# XBee.net
KiCad netlist of a schematic drawn in Altium Designer
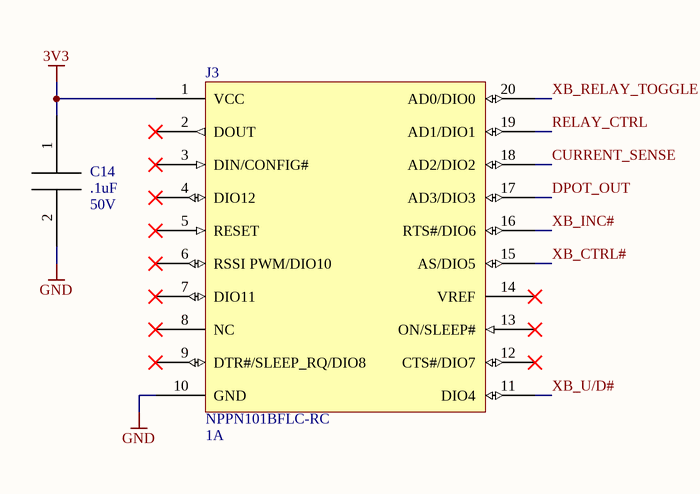
[diagram p0: XBee.SchDoc]

(export (version "E")
  (design (tool "Eeschema 10.0.6"))
  (components
    (comp (ref "C14")
      (value ".1uF")
      (footprint "0603")
      (fields (field (name "RATING") "50V") (field (name "Comment") "C_CAP_0603"))
      (libsource (lib "SeniorProject") (part "C_CAP_0603"))
    )
    (comp (ref "J3")
      (value "J_XBEE_NPPN101BFLC-RC")
      (footprint "NPPN101BFLC-RC")
      (fields
        (field (name "MANUFACTURER") "Sullins Connector Solutions")
        (field (name "PARTNUMBER") "NPPN101BFLC-RC")
        (field (name "RATING") "1A")
      )
      (libsource (lib "SeniorProject") (part "J_XBEE_NPPN101BFLC-RC"))
    )
  )
  (nets
    (net (code "1") (name "/CURRENT_SENSE") (class "Default")
      (node (ref "J3") (pin "18") (pinfunction "AD2/DIO2_18") (pintype "bidirectional"))
    )
    (net (code "2") (name "/DPOT_OUT") (class "Default")
      (node (ref "J3") (pin "17") (pinfunction "AD3/DIO3_17") (pintype "bidirectional"))
    )
    (net (code "3") (name "/RELAY_CTRL") (class "Default")
      (node (ref "J3") (pin "19") (pinfunction "AD1/DIO1_19") (pintype "bidirectional"))
    )
    (net (code "4") (name "/XB_CTRL#") (class "Default")
      (node (ref "J3") (pin "15") (pinfunction "AS/DIO5_15") (pintype "bidirectional"))
    )
    (net (code "5") (name "/XB_INC#") (class "Default")
      (node (ref "J3") (pin "16") (pinfunction "RTS#/DIO6_16") (pintype "bidirectional"))
    )
    (net (code "6") (name "/XB_RELAY_TOGGLE") (class "Default")
      (node (ref "J3") (pin "20") (pinfunction "AD0/DIO0_20") (pintype "bidirectional"))
    )
    (net (code "7") (name "/XB_U{slash}D#") (class "Default")
      (node (ref "J3") (pin "11") (pinfunction "DIO4_11") (pintype "bidirectional"))
    )
    (net (code "8") (name "3V3") (class "Default")
      (node (ref "C14") (pin "1") (pintype "passive"))
      (node (ref "J3") (pin "1") (pinfunction "VCC_1") (pintype "power_in"))
    )
    (net (code "9") (name "GND") (class "Default")
      (node (ref "C14") (pin "2") (pintype "passive"))
      (node (ref "J3") (pin "10") (pinfunction "GND_10") (pintype "power_in"))
    )
    (net (code "10") (name "unconnected-(J3-CTS#{slash}DIO7-Pad12)") (class "Default")
      (node (ref "J3") (pin "12") (pinfunction "CTS#/DIO7_12") (pintype "bidirectional+no_connect"))
    )
    (net (code "11") (name "unconnected-(J3-DIN{slash}CONFIG#-Pad3)") (class "Default")
      (node (ref "J3") (pin "3") (pinfunction "DIN/CONFIG#_3") (pintype "input+no_connect"))
    )
    (net (code "12") (name "unconnected-(J3-DIO11-Pad7)") (class "Default")
      (node (ref "J3") (pin "7") (pinfunction "DIO11_7") (pintype "bidirectional+no_connect"))
    )
    (net (code "13") (name "unconnected-(J3-DIO12-Pad4)") (class "Default")
      (node (ref "J3") (pin "4") (pinfunction "DIO12_4") (pintype "bidirectional+no_connect"))
    )
    (net (code "14") (name "unconnected-(J3-DOUT-Pad2)") (class "Default")
      (node (ref "J3") (pin "2") (pinfunction "DOUT_2") (pintype "output+no_connect"))
    )
    (net (code "15") (name "unconnected-(J3-DTR#{slash}SLEEP_RQ{slash}DIO8-Pad9)") (class "Default")
      (node (ref "J3") (pin "9") (pinfunction "DTR#/SLEEP_RQ/DIO8_9") (pintype "bidirectional+no_connect"))
    )
    (net (code "16") (name "unconnected-(J3-NC-Pad8)") (class "Default")
      (node (ref "J3") (pin "8") (pinfunction "NC_8") (pintype "passive+no_connect"))
    )
    (net (code "17") (name "unconnected-(J3-ON{slash}SLEEP#-Pad13)") (class "Default")
      (node (ref "J3") (pin "13") (pinfunction "ON/SLEEP#_13") (pintype "input+no_connect"))
    )
    (net (code "18") (name "unconnected-(J3-RESET-Pad5)") (class "Default")
      (node (ref "J3") (pin "5") (pinfunction "RESET_5") (pintype "input+no_connect"))
    )
    (net (code "19") (name "unconnected-(J3-RSSI_PWM{slash}DIO10-Pad6)") (class "Default")
      (node (ref "J3") (pin "6") (pinfunction "RSSI_PWM/DIO10_6") (pintype "bidirectional+no_connect"))
    )
    (net (code "20") (name "unconnected-(J3-VREF-Pad14)") (class "Default")
      (node (ref "J3") (pin "14") (pinfunction "VREF_14") (pintype "power_in+no_connect"))
    )
  )
)
